# Boost_stage_pwm_controller.net
KiCad netlist of a schematic drawn in Altium Designer
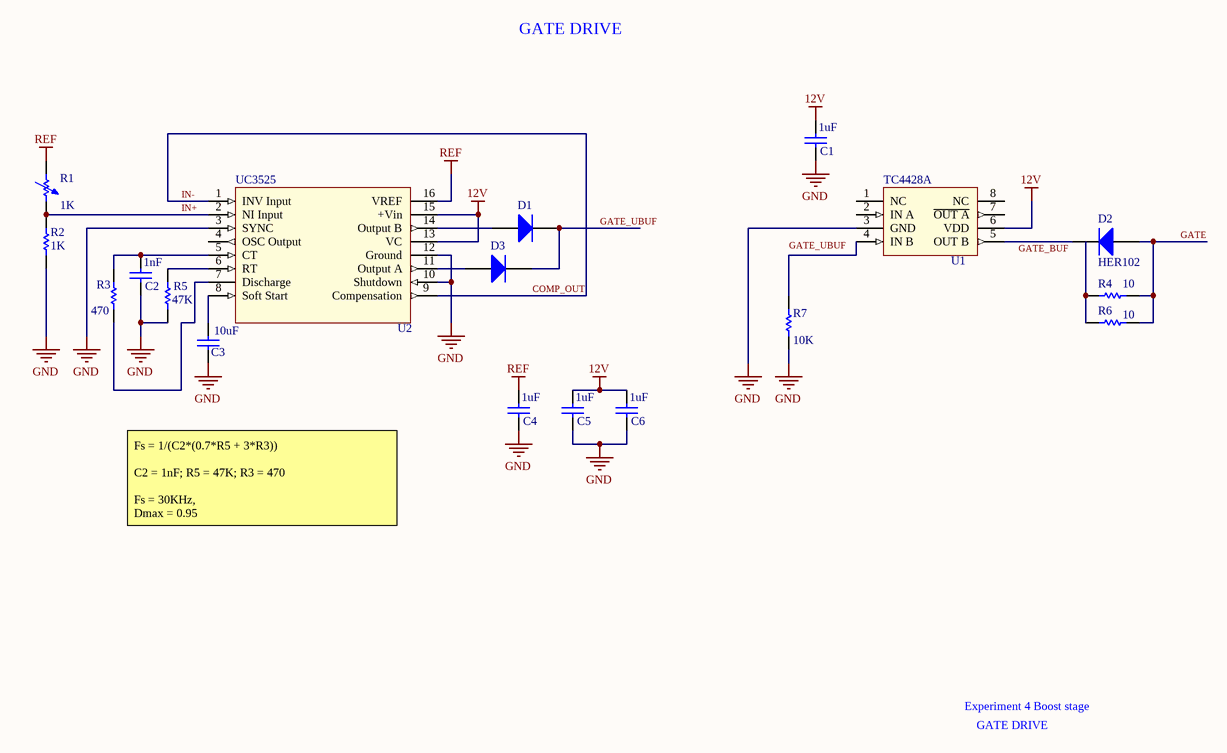
[diagram p0: Boost_stage_pwm_controller.SchDoc]

(export (version "E")
  (design (tool "Eeschema 10.0.6"))
  (components
    (comp (ref "C1")
      (value "1uF")
      (footprint "RAD-0.3")
      (description "Capacitor")
      (fields (field (name "Comment") "Cap") (field (name "PUBLISHER") "Altium Limited"))
      (libsource (lib "Miscellaneous Devices") (part "Cap"))
    )
    (comp (ref "C2")
      (value "1nF")
      (footprint "RAD-0.3")
      (description "Capacitor")
      (fields (field (name "Comment") "Cap") (field (name "PUBLISHER") "Altium Limited"))
      (libsource (lib "Miscellaneous Devices") (part "Cap"))
    )
    (comp (ref "C3")
      (value "10uF")
      (footprint "RAD-0.3")
      (description "Capacitor")
      (fields (field (name "Comment") "Cap") (field (name "PUBLISHER") "Altium Limited"))
      (libsource (lib "Miscellaneous Devices") (part "Cap"))
    )
    (comp (ref "C4")
      (value "1uF")
      (footprint "RAD-0.3")
      (description "Capacitor")
      (fields (field (name "Comment") "Cap") (field (name "PUBLISHER") "Altium Limited"))
      (libsource (lib "Miscellaneous Devices") (part "Cap"))
    )
    (comp (ref "C5")
      (value "1uF")
      (footprint "RAD-0.3")
      (description "Capacitor")
      (fields (field (name "Comment") "Cap") (field (name "PUBLISHER") "Altium Limited"))
      (libsource (lib "Miscellaneous Devices") (part "Cap"))
    )
    (comp (ref "C6")
      (value "1uF")
      (footprint "RAD-0.3")
      (description "Capacitor")
      (fields (field (name "Comment") "Cap") (field (name "PUBLISHER") "Altium Limited"))
      (libsource (lib "Miscellaneous Devices") (part "Cap"))
    )
    (comp (ref "D1")
      (value "Diode")
      (footprint "SMC")
      (description "Default Diode")
      (fields (field (name "PUBLISHER") "Altium Limited"))
      (libsource (lib "Miscellaneous Devices") (part "Diode"))
    )
    (comp (ref "D2")
      (value "HER102")
      (footprint "SMC")
      (description "Default Diode")
      (fields (field (name "PUBLISHER") "Altium Limited"))
      (libsource (lib "Miscellaneous Devices") (part "Diode"))
    )
    (comp (ref "D3")
      (value "Diode")
      (footprint "SMC")
      (description "Default Diode")
      (fields (field (name "PUBLISHER") "Altium Limited"))
      (libsource (lib "Miscellaneous Devices") (part "Diode"))
    )
    (comp (ref "R1")
      (value "1K")
      (footprint "AXIAL-0.7")
      (description "Variable Resistor")
      (fields (field (name "Comment") "Res Adj1") (field (name "PUBLISHER") "Altium Limited"))
      (libsource (lib "Miscellaneous Devices") (part "Res Adj1"))
    )
    (comp (ref "R2")
      (value "1K")
      (footprint "AXIAL-0.3")
      (description "Resistor")
      (fields (field (name "Comment") "Res1") (field (name "PUBLISHER") "Altium Limited"))
      (libsource (lib "Miscellaneous Devices") (part "Res1"))
    )
    (comp (ref "R3")
      (value "470")
      (footprint "AXIAL-0.3")
      (description "Resistor")
      (fields (field (name "Comment") "Res1") (field (name "PUBLISHER") "Altium Limited"))
      (libsource (lib "Miscellaneous Devices") (part "Res1"))
    )
    (comp (ref "R4")
      (value "10")
      (footprint "AXIAL-0.3")
      (description "Resistor")
      (fields (field (name "PUBLISHER") "Altium Limited"))
      (libsource (lib "Miscellaneous Devices") (part "Res1"))
    )
    (comp (ref "R5")
      (value "47K")
      (footprint "AXIAL-0.3")
      (description "Resistor")
      (fields (field (name "Comment") "Res1") (field (name "PUBLISHER") "Altium Limited"))
      (libsource (lib "Miscellaneous Devices") (part "Res1"))
    )
    (comp (ref "R6")
      (value "10")
      (footprint "AXIAL-0.3")
      (description "Resistor")
      (fields (field (name "PUBLISHER") "Altium Limited"))
      (libsource (lib "Miscellaneous Devices") (part "Res1"))
    )
    (comp (ref "R7")
      (value "10K")
      (footprint "AXIAL-0.3")
      (description "Resistor")
      (fields (field (name "PUBLISHER") "Altium Limited"))
      (libsource (lib "Miscellaneous Devices") (part "Res1"))
    )
    (comp (ref "U1") (value "TC4428A") (libsource (lib "*") (part "TC4428A")))
    (comp (ref "U2") (value "UC3525") (libsource (lib "*") (part "UC3525")))
  )
  (nets
    (net (code "1") (name "/COMP_OUT") (class "Default")
      (node (ref "U2") (pin "1") (pinfunction "INV_Input_1") (pintype "input"))
      (node (ref "U2") (pin "9") (pinfunction "Compensation_9") (pintype "output"))
    )
    (net (code "2") (name "/GATE") (class "Default")
      (node (ref "D2") (pin "1") (pinfunction "A_1") (pintype "passive"))
      (node (ref "R4") (pin "1") (pinfunction "1_1") (pintype "passive"))
      (node (ref "R6") (pin "1") (pinfunction "1_1") (pintype "passive"))
    )
    (net (code "4") (name "/GATE_UBUF") (class "Default")
      (node (ref "D1") (pin "2") (pinfunction "K_2") (pintype "passive"))
      (node (ref "D3") (pin "2") (pinfunction "K_2") (pintype "passive"))
    )
    (net (code "5") (name "/IN+") (class "Default")
      (node (ref "R1") (pin "2") (pinfunction "2_2") (pintype "passive"))
      (node (ref "R2") (pin "2") (pinfunction "2_2") (pintype "passive"))
      (node (ref "U2") (pin "2") (pinfunction "NI_Input_2") (pintype "input"))
    )
    (net (code "6") (name "12V") (class "Default")
      (node (ref "C1") (pin "2") (pinfunction "2_2") (pintype "passive"))
      (node (ref "C5") (pin "2") (pinfunction "2_2") (pintype "passive"))
      (node (ref "C6") (pin "2") (pinfunction "2_2") (pintype "passive"))
      (node (ref "U1") (pin "6") (pinfunction "VDD_6") (pintype "power_in"))
      (node (ref "U2") (pin "13") (pinfunction "VC_13") (pintype "power_in"))
      (node (ref "U2") (pin "15") (pinfunction "+Vin_15") (pintype "power_in"))
    )
    (net (code "7") (name "GND") (class "Default")
      (node (ref "C1") (pin "1") (pinfunction "1_1") (pintype "passive"))
      (node (ref "C2") (pin "1") (pinfunction "1_1") (pintype "passive"))
      (node (ref "C3") (pin "1") (pinfunction "1_1") (pintype "passive"))
      (node (ref "C4") (pin "1") (pinfunction "1_1") (pintype "passive"))
      (node (ref "C5") (pin "1") (pinfunction "1_1") (pintype "passive"))
      (node (ref "C6") (pin "1") (pinfunction "1_1") (pintype "passive"))
      (node (ref "R2") (pin "1") (pinfunction "1_1") (pintype "passive"))
      (node (ref "R5") (pin "1") (pinfunction "1_1") (pintype "passive"))
      (node (ref "R7") (pin "1") (pinfunction "1_1") (pintype "passive"))
      (node (ref "U1") (pin "3") (pinfunction "GND_3") (pintype "power_in"))
      (node (ref "U2") (pin "10") (pinfunction "Shutdown_10") (pintype "input"))
      (node (ref "U2") (pin "12") (pinfunction "Ground_12") (pintype "power_in"))
      (node (ref "U2") (pin "3") (pinfunction "SYNC_3") (pintype "input"))
    )
    (net (code "8") (name "Net-(D1-A)") (class "Default")
      (node (ref "D1") (pin "1") (pinfunction "A_1") (pintype "passive"))
      (node (ref "U2") (pin "14") (pinfunction "Output_B_14") (pintype "output"))
    )
    (net (code "9") (name "Net-(D2-K)") (class "Default")
      (node (ref "D2") (pin "2") (pinfunction "K_2") (pintype "passive"))
      (node (ref "U1") (pin "5") (pinfunction "OUT_B_5") (pintype "output"))
    )
    (net (code "10") (name "Net-(D3-A)") (class "Default")
      (node (ref "D3") (pin "1") (pinfunction "A_1") (pintype "passive"))
      (node (ref "U2") (pin "11") (pinfunction "Output_A_11") (pintype "output"))
    )
    (net (code "11") (name "Net-(R4-Pad2)") (class "Default")
      (node (ref "R4") (pin "2") (pinfunction "2_2") (pintype "passive"))
      (node (ref "R6") (pin "2") (pinfunction "2_2") (pintype "passive"))
    )
    (net (code "12") (name "Net-(U1-IN_B)") (class "Default")
      (node (ref "R7") (pin "2") (pinfunction "2_2") (pintype "passive"))
      (node (ref "U1") (pin "4") (pinfunction "IN_B_4") (pintype "input"))
    )
    (net (code "13") (name "Net-(U2-CT)") (class "Default")
      (node (ref "C2") (pin "2") (pinfunction "2_2") (pintype "passive"))
      (node (ref "R3") (pin "1") (pinfunction "1_1") (pintype "passive"))
      (node (ref "U2") (pin "5") (pinfunction "CT_5") (pintype "input"))
    )
    (net (code "14") (name "Net-(U2-Discharge)") (class "Default")
      (node (ref "R3") (pin "2") (pinfunction "2_2") (pintype "passive"))
      (node (ref "U2") (pin "7") (pinfunction "Discharge_7") (pintype "open_collector"))
    )
    (net (code "15") (name "Net-(U2-RT)") (class "Default")
      (node (ref "R5") (pin "2") (pinfunction "2_2") (pintype "passive"))
      (node (ref "U2") (pin "6") (pinfunction "RT_6") (pintype "input"))
    )
    (net (code "16") (name "Net-(U2-Soft_Start)") (class "Default")
      (node (ref "C3") (pin "2") (pinfunction "2_2") (pintype "passive"))
      (node (ref "U2") (pin "8") (pinfunction "Soft_Start_8") (pintype "input"))
    )
    (net (code "17") (name "REF") (class "Default")
      (node (ref "C4") (pin "2") (pinfunction "2_2") (pintype "passive"))
      (node (ref "R1") (pin "1") (pinfunction "1_1") (pintype "passive"))
      (node (ref "U2") (pin "16") (pinfunction "VREF_16") (pintype "power_in"))
    )
    (net (code "18") (name "unconnected-(U1-IN_A-Pad2)") (class "Default")
      (node (ref "U1") (pin "2") (pinfunction "IN_A_2") (pintype "input"))
    )
    (net (code "19") (name "unconnected-(U1-NC-Pad1)") (class "Default")
      (node (ref "U1") (pin "1") (pinfunction "NC_1") (pintype "power_in"))
    )
    (net (code "20") (name "unconnected-(U1-NC-Pad8)") (class "Default")
      (node (ref "U1") (pin "8") (pinfunction "NC_8") (pintype "power_in"))
    )
    (net (code "21") (name "unconnected-(U1-~{OUT_A}-Pad7)") (class "Default")
      (node (ref "U1") (pin "7") (pinfunction "~{OUT_A}_7") (pintype "output"))
    )
    (net (code "22") (name "unconnected-(U2-OSC_Output-Pad4)") (class "Default")
      (node (ref "U2") (pin "4") (pinfunction "OSC_Output_4") (pintype "output"))
    )
  )
)
